# 3V3.net
KiCad netlist of a schematic drawn in Altium Designer
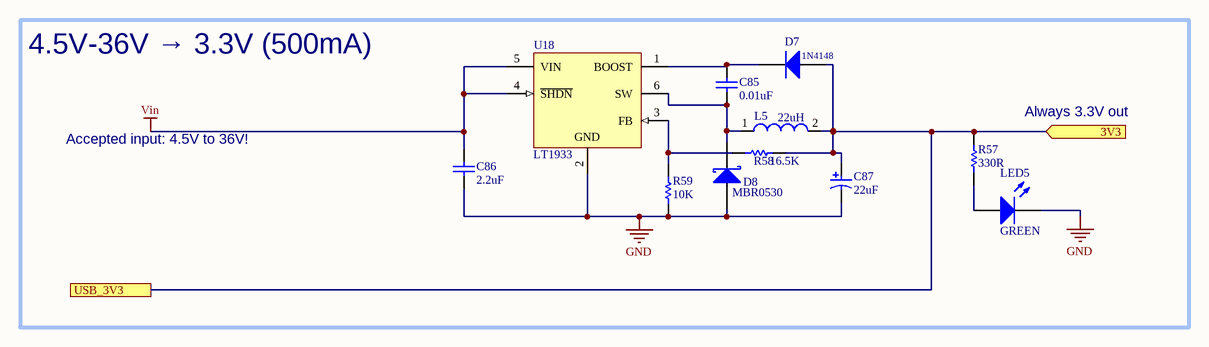
[diagram p0: 3V3.SchDoc]

(export (version "E")
  (design (tool "Eeschema 10.0.6"))
  (components
    (comp (ref "C85")
      (value "0.01uF")
      (footprint "CAPC1608X87X35NL15T15")
      (description "0.01uF 0603 50V")
      (fields (field (name "MANUFACTURER") "Kemet") (field (name "PART NUMBER") "C0603C101J5GACTU"))
      (libsource (lib "Altium Content Vault") (part "CAP"))
    )
    (comp (ref "C86")
      (value "2.2uF")
      (footprint "CAPC2013X135X45ML10T25")
      (fields (field (name "PART NUMBER") "GRM21BF51E225ZA01L") (field (name "MANUFACTURER") "Murata"))
      (libsource (lib "Altium Content Vault") (part "CAP"))
    )
    (comp (ref "C87")
      (value "22uF")
      (footprint "PNSC-EEE-FK1H220P_L")
      (description "Cap Aluminum Lytic, 22 uF, +/- 20%, 6.3 to 100 V, -55 to 105 degC, 2-Pin SMD, RoHS, Tape and Reel")
      (fields (field (name "MANUFACTURER") "Panasonic"))
      (libsource (lib "Altium Content Vault") (part "CAP-P-2"))
    )
    (comp (ref "D7")
      (value "1N4148")
      (footprint "DIOD-SOD123-2_V")
      (description "Fast Switching Diode, 100 V, 0.15 A, -65 to 150 degC, 2-Pin?SOD123, RoHS, Tape and Reel")
      (fields (field (name "MANUFACTURER") "DiodesIncorporated"))
      (libsource (lib "Altium Content Vault") (part "D-AK-2"))
    )
    (comp (ref "D8")
      (value "MBR0530")
      (footprint "FAIR-SOD123-2_V")
      (description "Diode Schottky 30V 0.5A 2-Pin SOD-123 T/R")
      (fields (field (name "MANUFACTURER") "Fairchild"))
      (libsource (lib "Altium Content Vault") (part "DSKY-AK-2"))
    )
    (comp (ref "L5")
      (value "22uH")
      (footprint "WE-PD-XL")
      (description "SMD-Shielded Power Inductor WE-PD, L = 22.0 µH")
      (libsource (lib "Altium Content Vault") (part "PAS-IND-INDUCTOR-2"))
    )
    (comp (ref "LED5")
      (value "GREEN")
      (footprint "0603_A")
      (description "SMD mono-color Chip LED, WL-SMCW, Bright Green")
      (fields (field (name "PARTNUMBER") "150060VS75000") (field (name "MANUFACTURER") "Wuerth Elektronik"))
      (libsource (lib "Altium Content Vault") (part "WE-LED_K1A2-2"))
    )
    (comp (ref "R57")
      (value "330R")
      (footprint "RESC0603(1608)_L")
      (description "330R 0.1W 5% 0603 (1608 Metric)  SMD")
      (fields (field (name "TOLERANCE") "5 %") (field (name "POWER") "0.1 W"))
      (libsource (lib "Altium Content Vault") (part "RES"))
    )
    (comp (ref "R58")
      (value "16.5K")
      (footprint "RESC0603(1608)_L")
      (description "16.5K 0.1W 5% 0603 (1608 Metric)  SMD")
      (fields (field (name "TOLERANCE") "5 %") (field (name "POWER") "0.1 W"))
      (libsource (lib "Altium Content Vault") (part "RES"))
    )
    (comp (ref "R59")
      (value "10K")
      (footprint "RESC0603(1608)_L")
      (description "10K 0.1W 5% 0603 (1608 Metric)  SMD")
      (fields (field (name "TOLERANCE") "5 %") (field (name "POWER") "0.1 W"))
      (libsource (lib "Altium Content Vault") (part "RES"))
    )
    (comp (ref "U18")
      (value "LT1933")
      (footprint "LT-S6-6-SOT-23_L")
      (fields (field (name "PARTNUMBER") "LT1933ES6#TRPBF") (field (name "MANUFACTURER") "Linear Technology"))
      (libsource (lib "Altium Content Vault") (part "LT-LT1616_1933_1934_1934-1"))
    )
  )
  (nets
    (net (code "1") (name "/3V3") (class "Default")
      (node (ref "C87") (pin "1") (pinfunction "1_1") (pintype "passive"))
      (node (ref "D7") (pin "1") (pinfunction "A_1") (pintype "passive"))
      (node (ref "L5") (pin "2") (pinfunction "2_2") (pintype "passive"))
      (node (ref "R57") (pin "2") (pinfunction "2_2") (pintype "passive"))
      (node (ref "R58") (pin "1") (pinfunction "1_1") (pintype "passive"))
    )
    (net (code "2") (name "GND") (class "Default")
      (node (ref "C86") (pin "1") (pinfunction "1_1") (pintype "passive"))
      (node (ref "C87") (pin "2") (pinfunction "2_2") (pintype "passive"))
      (node (ref "D8") (pin "1") (pinfunction "A_1") (pintype "passive"))
      (node (ref "LED5") (pin "1") (pinfunction "K_1") (pintype "passive"))
      (node (ref "R59") (pin "1") (pinfunction "1_1") (pintype "passive"))
      (node (ref "U18") (pin "2") (pinfunction "GND_2") (pintype "power_in"))
    )
    (net (code "3") (name "Net-(D7-K)") (class "Default")
      (node (ref "C85") (pin "2") (pinfunction "2_2") (pintype "passive"))
      (node (ref "D7") (pin "2") (pinfunction "K_2") (pintype "passive"))
      (node (ref "U18") (pin "1") (pinfunction "BOOST_1") (pintype "passive"))
    )
    (net (code "4") (name "Net-(D8-K)") (class "Default")
      (node (ref "C85") (pin "1") (pinfunction "1_1") (pintype "passive"))
      (node (ref "D8") (pin "2") (pinfunction "K_2") (pintype "passive"))
      (node (ref "L5") (pin "1") (pinfunction "1_1") (pintype "passive"))
      (node (ref "U18") (pin "6") (pinfunction "SW_6") (pintype "power_in"))
    )
    (net (code "5") (name "Net-(LED5-A)") (class "Default")
      (node (ref "LED5") (pin "2") (pinfunction "A_2") (pintype "passive"))
      (node (ref "R57") (pin "1") (pinfunction "1_1") (pintype "passive"))
    )
    (net (code "6") (name "Net-(U18-FB)") (class "Default")
      (node (ref "R58") (pin "2") (pinfunction "2_2") (pintype "passive"))
      (node (ref "R59") (pin "2") (pinfunction "2_2") (pintype "passive"))
      (node (ref "U18") (pin "3") (pinfunction "FB_3") (pintype "input"))
    )
    (net (code "7") (name "Vin") (class "Default")
      (node (ref "C86") (pin "2") (pinfunction "2_2") (pintype "passive"))
      (node (ref "U18") (pin "4") (pinfunction "~{SHDN}_4") (pintype "input"))
      (node (ref "U18") (pin "5") (pinfunction "VIN_5") (pintype "power_in"))
    )
  )
)
